# AMC-SATA.net
KiCad netlist of a schematic drawn in Altium Designer
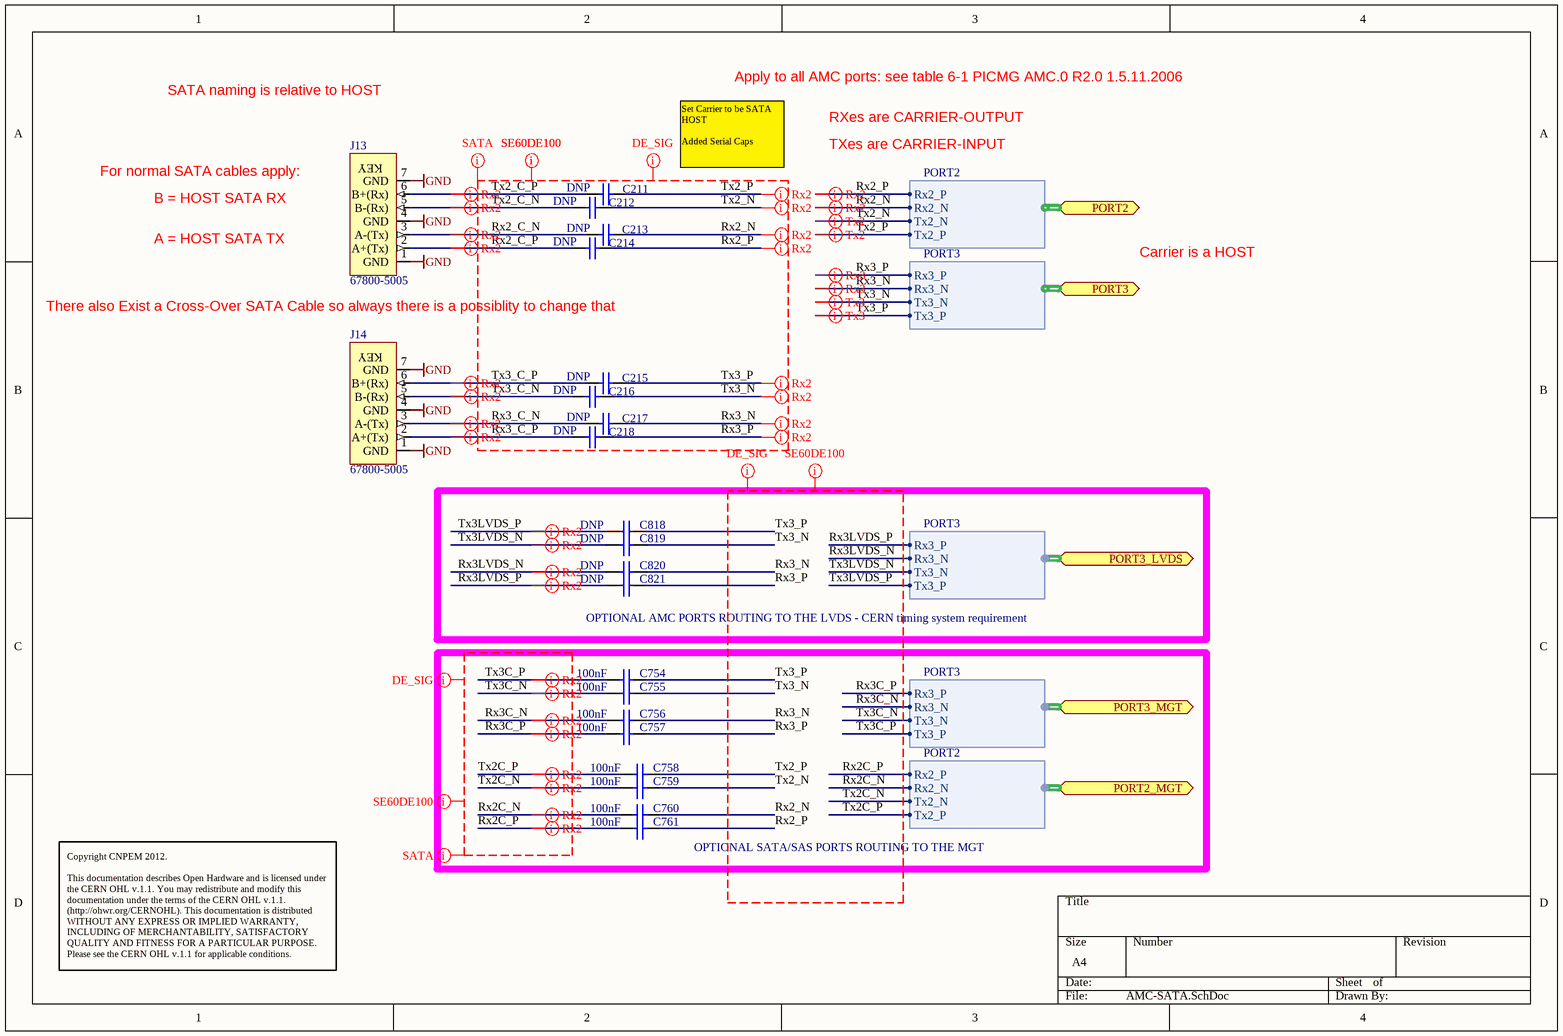
[diagram p0: AMC-SATA.SchDoc]

(export (version "E")
  (design (tool "Eeschema 10.0.6"))
  (components
    (comp (ref "C211")
      (value "DNP")
      (footprint "CAPC0603X33N")
      (description "Non-polarised capacitor")
      (fields
        (field (name "PART NUMBER") "CC0201_100NF_6.3V_10%_X5R")
        (field (name "VOLTAGE") "6.3V")
        (field (name "AUTHOR") "CERN DEM JLC")
      )
      (libsource (lib "Capacitors") (part "Capacitor - non polarized"))
    )
    (comp (ref "C212")
      (value "DNP")
      (footprint "CAPC0603X33N")
      (description "Non-polarised capacitor")
      (fields
        (field (name "PART NUMBER") "CC0201_100NF_6.3V_10%_X5R")
        (field (name "VOLTAGE") "6.3V")
        (field (name "AUTHOR") "CERN DEM JLC")
      )
      (libsource (lib "Capacitors") (part "Capacitor - non polarized"))
    )
    (comp (ref "C213")
      (value "DNP")
      (footprint "CAPC0603X33N")
      (description "Non-polarised capacitor")
      (fields
        (field (name "PART NUMBER") "CC0201_100NF_6.3V_10%_X5R")
        (field (name "VOLTAGE") "6.3V")
        (field (name "AUTHOR") "CERN DEM JLC")
      )
      (libsource (lib "Capacitors") (part "Capacitor - non polarized"))
    )
    (comp (ref "C214")
      (value "DNP")
      (footprint "CAPC0603X33N")
      (description "Non-polarised capacitor")
      (fields
        (field (name "PART NUMBER") "CC0201_100NF_6.3V_10%_X5R")
        (field (name "VOLTAGE") "6.3V")
        (field (name "AUTHOR") "CERN DEM JLC")
      )
      (libsource (lib "Capacitors") (part "Capacitor - non polarized"))
    )
    (comp (ref "C215")
      (value "DNP")
      (footprint "CAPC0603X33N")
      (description "Non-polarised capacitor")
      (fields
        (field (name "PART NUMBER") "CC0201_100NF_6.3V_10%_X5R")
        (field (name "VOLTAGE") "6.3V")
        (field (name "AUTHOR") "CERN DEM JLC")
      )
      (libsource (lib "Capacitors") (part "Capacitor - non polarized"))
    )
    (comp (ref "C216")
      (value "DNP")
      (footprint "CAPC0603X33N")
      (description "Non-polarised capacitor")
      (fields
        (field (name "PART NUMBER") "CC0201_100NF_6.3V_10%_X5R")
        (field (name "VOLTAGE") "6.3V")
        (field (name "AUTHOR") "CERN DEM JLC")
      )
      (libsource (lib "Capacitors") (part "Capacitor - non polarized"))
    )
    (comp (ref "C217")
      (value "DNP")
      (footprint "CAPC0603X33N")
      (description "Non-polarised capacitor")
      (fields
        (field (name "PART NUMBER") "CC0201_100NF_6.3V_10%_X5R")
        (field (name "VOLTAGE") "6.3V")
        (field (name "AUTHOR") "CERN DEM JLC")
      )
      (libsource (lib "Capacitors") (part "Capacitor - non polarized"))
    )
    (comp (ref "C218")
      (value "DNP")
      (footprint "CAPC0603X33N")
      (description "Non-polarised capacitor")
      (fields
        (field (name "PART NUMBER") "CC0201_100NF_6.3V_10%_X5R")
        (field (name "VOLTAGE") "6.3V")
        (field (name "AUTHOR") "CERN DEM JLC")
      )
      (libsource (lib "Capacitors") (part "Capacitor - non polarized"))
    )
    (comp (ref "C754")
      (value "100nF")
      (footprint "CAPC0603X33N")
      (description "Non-polarised capacitor")
      (fields
        (field (name "PART NUMBER") "CC0201_100NF_6.3V_10%_X5R")
        (field (name "VOLTAGE") "6.3V")
        (field (name "AUTHOR") "CERN DEM JLC")
      )
      (libsource (lib "Capacitors") (part "Capacitor - non polarized"))
    )
    (comp (ref "C755")
      (value "100nF")
      (footprint "CAPC0603X33N")
      (description "Non-polarised capacitor")
      (fields
        (field (name "PART NUMBER") "CC0201_100NF_6.3V_10%_X5R")
        (field (name "VOLTAGE") "6.3V")
        (field (name "AUTHOR") "CERN DEM JLC")
      )
      (libsource (lib "Capacitors") (part "Capacitor - non polarized"))
    )
    (comp (ref "C756")
      (value "100nF")
      (footprint "CAPC0603X33N")
      (description "Non-polarised capacitor")
      (fields
        (field (name "PART NUMBER") "CC0201_100NF_6.3V_10%_X5R")
        (field (name "VOLTAGE") "6.3V")
        (field (name "AUTHOR") "CERN DEM JLC")
      )
      (libsource (lib "Capacitors") (part "Capacitor - non polarized"))
    )
    (comp (ref "C757")
      (value "100nF")
      (footprint "CAPC0603X33N")
      (description "Non-polarised capacitor")
      (fields
        (field (name "PART NUMBER") "CC0201_100NF_6.3V_10%_X5R")
        (field (name "VOLTAGE") "6.3V")
        (field (name "AUTHOR") "CERN DEM JLC")
      )
      (libsource (lib "Capacitors") (part "Capacitor - non polarized"))
    )
    (comp (ref "C758")
      (value "100nF")
      (footprint "CAPC0603X33N")
      (description "Non-polarised capacitor")
      (fields
        (field (name "PART NUMBER") "CC0201_100NF_6.3V_10%_X5R")
        (field (name "VOLTAGE") "6.3V")
        (field (name "AUTHOR") "CERN DEM JLC")
      )
      (libsource (lib "Capacitors") (part "Capacitor - non polarized"))
    )
    (comp (ref "C759")
      (value "100nF")
      (footprint "CAPC0603X33N")
      (description "Non-polarised capacitor")
      (fields
        (field (name "PART NUMBER") "CC0201_100NF_6.3V_10%_X5R")
        (field (name "VOLTAGE") "6.3V")
        (field (name "AUTHOR") "CERN DEM JLC")
      )
      (libsource (lib "Capacitors") (part "Capacitor - non polarized"))
    )
    (comp (ref "C760")
      (value "100nF")
      (footprint "CAPC0603X33N")
      (description "Non-polarised capacitor")
      (fields
        (field (name "PART NUMBER") "CC0201_100NF_6.3V_10%_X5R")
        (field (name "VOLTAGE") "6.3V")
        (field (name "AUTHOR") "CERN DEM JLC")
      )
      (libsource (lib "Capacitors") (part "Capacitor - non polarized"))
    )
    (comp (ref "C761")
      (value "100nF")
      (footprint "CAPC0603X33N")
      (description "Non-polarised capacitor")
      (fields
        (field (name "PART NUMBER") "CC0201_100NF_6.3V_10%_X5R")
        (field (name "VOLTAGE") "6.3V")
        (field (name "AUTHOR") "CERN DEM JLC")
      )
      (libsource (lib "Capacitors") (part "Capacitor - non polarized"))
    )
    (comp (ref "C818")
      (value "DNP")
      (footprint "CAPC0603X33N")
      (description "Non-polarised capacitor")
      (fields
        (field (name "PART NUMBER") "CC0201_100NF_6.3V_10%_X5R")
        (field (name "VOLTAGE") "6.3V")
        (field (name "AUTHOR") "CERN DEM JLC")
      )
      (libsource (lib "Capacitors") (part "Capacitor - non polarized"))
    )
    (comp (ref "C819")
      (value "DNP")
      (footprint "CAPC0603X33N")
      (description "Non-polarised capacitor")
      (fields
        (field (name "PART NUMBER") "CC0201_100NF_6.3V_10%_X5R")
        (field (name "VOLTAGE") "6.3V")
        (field (name "AUTHOR") "CERN DEM JLC")
      )
      (libsource (lib "Capacitors") (part "Capacitor - non polarized"))
    )
    (comp (ref "C820")
      (value "DNP")
      (footprint "CAPC0603X33N")
      (description "Non-polarised capacitor")
      (fields
        (field (name "PART NUMBER") "CC0201_100NF_6.3V_10%_X5R")
        (field (name "VOLTAGE") "6.3V")
        (field (name "AUTHOR") "CERN DEM JLC")
      )
      (libsource (lib "Capacitors") (part "Capacitor - non polarized"))
    )
    (comp (ref "C821")
      (value "DNP")
      (footprint "CAPC0603X33N")
      (description "Non-polarised capacitor")
      (fields
        (field (name "PART NUMBER") "CC0201_100NF_6.3V_10%_X5R")
        (field (name "VOLTAGE") "6.3V")
        (field (name "AUTHOR") "CERN DEM JLC")
      )
      (libsource (lib "Capacitors") (part "Capacitor - non polarized"))
    )
    (comp (ref "J13")
      (value "67800-5005")
      (footprint "CON_SATA_V")
      (description "SATA conenctor  PCB Molex")
      (libsource (lib "AMC_FMC_Carrier") (part "CON_SATA_V"))
    )
    (comp (ref "J14")
      (value "67800-5005")
      (footprint "CON_SATA_V")
      (description "SATA conenctor  PCB Molex")
      (libsource (lib "AMC_FMC_Carrier") (part "CON_SATA_V"))
    )
  )
  (nets
    (net (code "3") (name "/Rx2C_N") (class "Default")
      (node (ref "C760") (pin "1") (pinfunction "1_1") (pintype "passive"))
    )
    (net (code "4") (name "/Rx2C_P") (class "Default")
      (node (ref "C761") (pin "1") (pinfunction "1_1") (pintype "passive"))
    )
    (net (code "5") (name "/Rx2_C_N") (class "Default")
      (node (ref "C213") (pin "1") (pinfunction "1_1") (pintype "passive"))
      (node (ref "J13") (pin "3") (pinfunction "A-(Tx)_3") (pintype "output"))
    )
    (net (code "6") (name "/Rx2_C_P") (class "Default")
      (node (ref "C214") (pin "1") (pinfunction "1_1") (pintype "passive"))
      (node (ref "J13") (pin "2") (pinfunction "A+(Tx)_2") (pintype "output"))
    )
    (net (code "7") (name "/Rx2_N") (class "Default")
      (node (ref "C213") (pin "2") (pinfunction "2_2") (pintype "passive"))
      (node (ref "C760") (pin "2") (pinfunction "2_2") (pintype "passive"))
    )
    (net (code "8") (name "/Rx2_P") (class "Default")
      (node (ref "C214") (pin "2") (pinfunction "2_2") (pintype "passive"))
      (node (ref "C761") (pin "2") (pinfunction "2_2") (pintype "passive"))
    )
    (net (code "9") (name "/Rx3C_N") (class "Default")
      (node (ref "C756") (pin "1") (pinfunction "1_1") (pintype "passive"))
    )
    (net (code "10") (name "/Rx3C_P") (class "Default")
      (node (ref "C757") (pin "1") (pinfunction "1_1") (pintype "passive"))
    )
    (net (code "11") (name "/Rx3LVDS_N") (class "Default")
      (node (ref "C820") (pin "1") (pinfunction "1_1") (pintype "passive"))
    )
    (net (code "12") (name "/Rx3LVDS_P") (class "Default")
      (node (ref "C821") (pin "1") (pinfunction "1_1") (pintype "passive"))
    )
    (net (code "13") (name "/Rx3_C_N") (class "Default")
      (node (ref "C217") (pin "1") (pinfunction "1_1") (pintype "passive"))
      (node (ref "J14") (pin "3") (pinfunction "A-(Tx)_3") (pintype "output"))
    )
    (net (code "14") (name "/Rx3_C_P") (class "Default")
      (node (ref "C218") (pin "1") (pinfunction "1_1") (pintype "passive"))
      (node (ref "J14") (pin "2") (pinfunction "A+(Tx)_2") (pintype "output"))
    )
    (net (code "15") (name "/Rx3_N") (class "Default")
      (node (ref "C217") (pin "2") (pinfunction "2_2") (pintype "passive"))
      (node (ref "C756") (pin "2") (pinfunction "2_2") (pintype "passive"))
      (node (ref "C820") (pin "2") (pinfunction "2_2") (pintype "passive"))
    )
    (net (code "16") (name "/Rx3_P") (class "Default")
      (node (ref "C218") (pin "2") (pinfunction "2_2") (pintype "passive"))
      (node (ref "C757") (pin "2") (pinfunction "2_2") (pintype "passive"))
      (node (ref "C821") (pin "2") (pinfunction "2_2") (pintype "passive"))
    )
    (net (code "17") (name "/Tx2C_N") (class "Default")
      (node (ref "C759") (pin "1") (pinfunction "1_1") (pintype "passive"))
    )
    (net (code "18") (name "/Tx2C_P") (class "Default")
      (node (ref "C758") (pin "1") (pinfunction "1_1") (pintype "passive"))
    )
    (net (code "19") (name "/Tx2_C_N") (class "Default")
      (node (ref "C212") (pin "1") (pinfunction "1_1") (pintype "passive"))
      (node (ref "J13") (pin "5") (pinfunction "B-(Rx)_5") (pintype "input"))
    )
    (net (code "20") (name "/Tx2_C_P") (class "Default")
      (node (ref "C211") (pin "1") (pinfunction "1_1") (pintype "passive"))
      (node (ref "J13") (pin "6") (pinfunction "B+(Rx)_6") (pintype "input"))
    )
    (net (code "21") (name "/Tx2_N") (class "Default")
      (node (ref "C212") (pin "2") (pinfunction "2_2") (pintype "passive"))
      (node (ref "C759") (pin "2") (pinfunction "2_2") (pintype "passive"))
    )
    (net (code "22") (name "/Tx2_P") (class "Default")
      (node (ref "C211") (pin "2") (pinfunction "2_2") (pintype "passive"))
      (node (ref "C758") (pin "2") (pinfunction "2_2") (pintype "passive"))
    )
    (net (code "23") (name "/Tx3C_N") (class "Default")
      (node (ref "C755") (pin "1") (pinfunction "1_1") (pintype "passive"))
    )
    (net (code "24") (name "/Tx3C_P") (class "Default")
      (node (ref "C754") (pin "1") (pinfunction "1_1") (pintype "passive"))
    )
    (net (code "25") (name "/Tx3LVDS_N") (class "Default")
      (node (ref "C819") (pin "1") (pinfunction "1_1") (pintype "passive"))
    )
    (net (code "26") (name "/Tx3LVDS_P") (class "Default")
      (node (ref "C818") (pin "1") (pinfunction "1_1") (pintype "passive"))
    )
    (net (code "27") (name "/Tx3_C_N") (class "Default")
      (node (ref "C216") (pin "1") (pinfunction "1_1") (pintype "passive"))
      (node (ref "J14") (pin "5") (pinfunction "B-(Rx)_5") (pintype "input"))
    )
    (net (code "28") (name "/Tx3_C_P") (class "Default")
      (node (ref "C215") (pin "1") (pinfunction "1_1") (pintype "passive"))
      (node (ref "J14") (pin "6") (pinfunction "B+(Rx)_6") (pintype "input"))
    )
    (net (code "29") (name "/Tx3_N") (class "Default")
      (node (ref "C216") (pin "2") (pinfunction "2_2") (pintype "passive"))
      (node (ref "C755") (pin "2") (pinfunction "2_2") (pintype "passive"))
      (node (ref "C819") (pin "2") (pinfunction "2_2") (pintype "passive"))
    )
    (net (code "30") (name "/Tx3_P") (class "Default")
      (node (ref "C215") (pin "2") (pinfunction "2_2") (pintype "passive"))
      (node (ref "C754") (pin "2") (pinfunction "2_2") (pintype "passive"))
      (node (ref "C818") (pin "2") (pinfunction "2_2") (pintype "passive"))
    )
    (net (code "33") (name "GND") (class "Default")
      (node (ref "J13") (pin "1") (pinfunction "GND_1") (pintype "power_in"))
      (node (ref "J13") (pin "4") (pinfunction "GND_4") (pintype "power_in"))
      (node (ref "J13") (pin "7") (pinfunction "GND_7") (pintype "power_in"))
      (node (ref "J14") (pin "1") (pinfunction "GND_1") (pintype "power_in"))
      (node (ref "J14") (pin "4") (pinfunction "GND_4") (pintype "power_in"))
      (node (ref "J14") (pin "7") (pinfunction "GND_7") (pintype "power_in"))
    )
  )
)
